# Low_Pass_Filter.net
KiCad netlist of a schematic drawn in Altium Designer
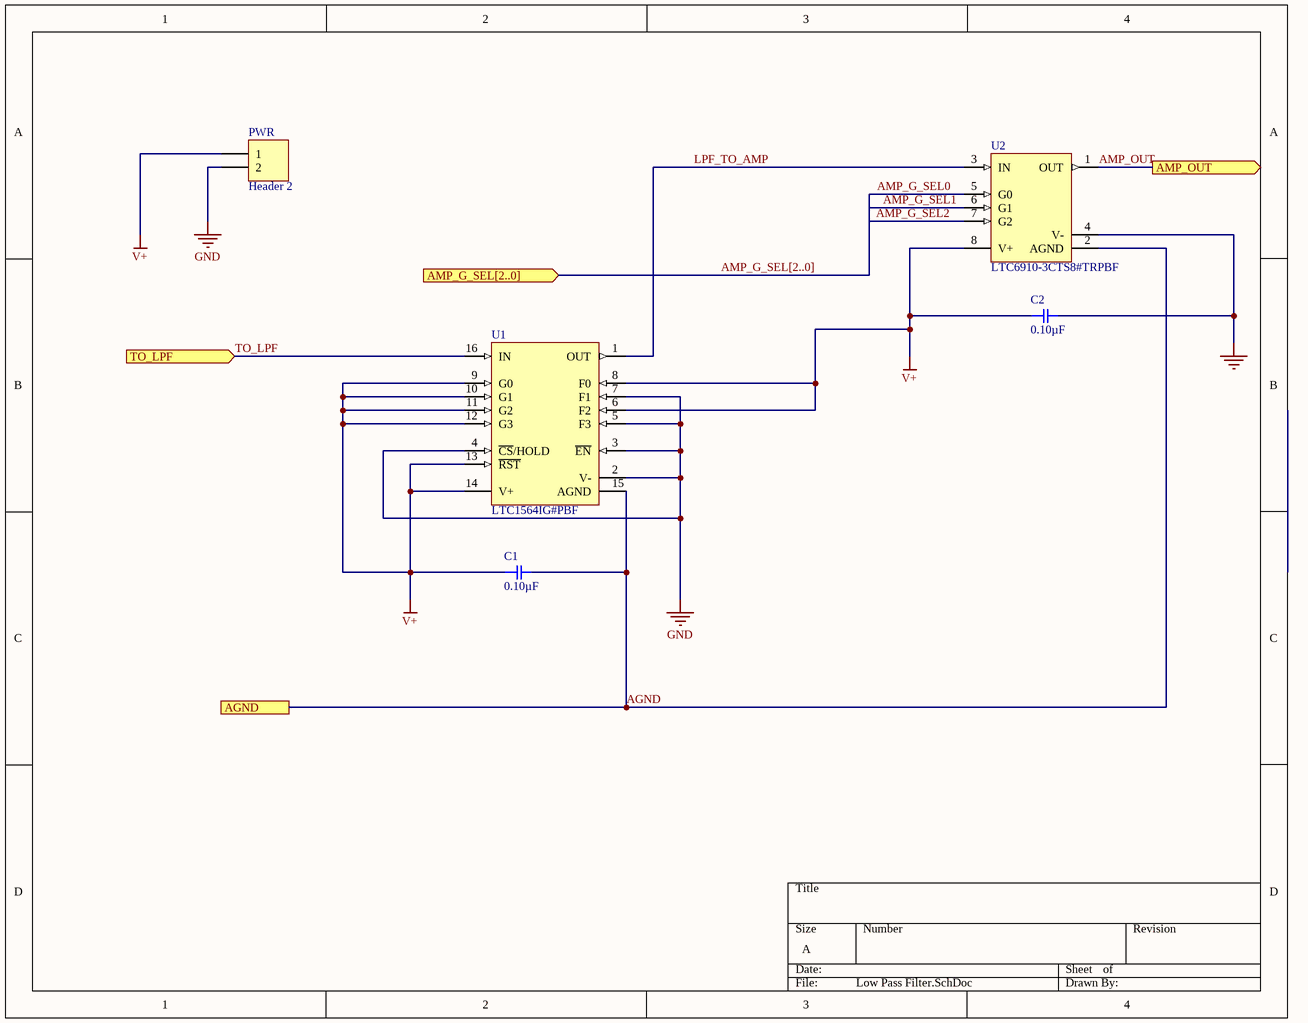
[diagram p0: Low Pass Filter.SchDoc]

(export (version "E")
  (design (tool "Eeschema 10.0.6"))
  (components
    (comp (ref "C1")
      (value "0.10µF")
      (footprint "SMD-0805C")
      (description "CAP CER 0.1UF 50V X7R 0805")
      (fields
        (field (name "DIGI-KEY PART NUMBER") "490-11955-1-ND")
        (field (name "PART NUMBER") "GCD21BR71H104KA01L")
      )
      (libsource (lib "capacitor_murata_0805") (part "GCD21BR71H104KA01L"))
    )
    (comp (ref "C2")
      (value "0.10µF")
      (footprint "SMD-0805C")
      (description "CAP CER 0.1UF 50V X7R 0805")
      (fields
        (field (name "DIGI-KEY PART NUMBER") "490-11955-1-ND")
        (field (name "PART NUMBER") "GCD21BR71H104KA01L")
      )
      (libsource (lib "capacitor_murata_0805") (part "GCD21BR71H104KA01L"))
    )
    (comp (ref "PWR")
      (value "Header 2")
      (footprint "HDR1X2")
      (description "Header, 2-Pin")
      (fields (field (name "PUBLISHER") "Altium Limited"))
      (libsource (lib "Miscellaneous Connectors") (part "Header 2"))
    )
    (comp (ref "U1")
      (value "LTC1564IG#PBF")
      (footprint "LT-G-16_M")
      (fields
        (field (name "LINEAR TECHNOLOGY PART NUMBER") "LTC1564")
        (field (name "MANUFACTURER") "Linear Technology")
      )
      (libsource (lib "Altium Content Vault") (part "LT-LTC1564-G-16"))
    )
    (comp (ref "U2")
      (value "LTC6910-3CTS8#TRPBF")
      (footprint "LT-TS8-8-TSOT-23_V")
      (fields
        (field (name "MANUFACTURER") "Linear Technology")
        (field (name "LINEAR TECHNOLOGY PART NUMBER") "LTC6910-3")
      )
      (libsource (lib "Altium Content Vault") (part "LT-LTC6910-TS8-8"))
    )
  )
  (nets
    (net (code "1") (name "/AGND") (class "Default")
      (node (ref "C1") (pin "2") (pinfunction "2_2") (pintype "passive"))
      (node (ref "U1") (pin "15") (pinfunction "AGND_15") (pintype "power_in"))
      (node (ref "U2") (pin "2") (pinfunction "AGND_2") (pintype "power_in"))
    )
    (net (code "2") (name "/AMP_G_SEL0") (class "Default")
      (node (ref "U2") (pin "5") (pinfunction "G0_5") (pintype "input"))
    )
    (net (code "3") (name "/AMP_G_SEL1") (class "Default")
      (node (ref "U2") (pin "6") (pinfunction "G1_6") (pintype "input"))
    )
    (net (code "4") (name "/AMP_G_SEL2") (class "Default")
      (node (ref "U2") (pin "7") (pinfunction "G2_7") (pintype "input"))
    )
    (net (code "6") (name "/AMP_OUT") (class "Default")
      (node (ref "U2") (pin "1") (pinfunction "OUT_1") (pintype "output"))
    )
    (net (code "7") (name "/LPF_TO_AMP") (class "Default")
      (node (ref "U1") (pin "1") (pinfunction "OUT_1") (pintype "output"))
      (node (ref "U2") (pin "3") (pinfunction "IN_3") (pintype "input"))
    )
    (net (code "8") (name "/TO_LPF") (class "Default")
      (node (ref "U1") (pin "16") (pinfunction "IN_16") (pintype "input"))
    )
    (net (code "9") (name "GND") (class "Default")
      (node (ref "C2") (pin "2") (pinfunction "2_2") (pintype "passive"))
      (node (ref "PWR") (pin "2") (pinfunction "2_2") (pintype "passive"))
      (node (ref "U1") (pin "2") (pinfunction "V-_2") (pintype "power_in"))
      (node (ref "U1") (pin "3") (pinfunction "~{EN}_3") (pintype "input"))
      (node (ref "U1") (pin "4") (pinfunction "~{CS}/HOLD_4") (pintype "input"))
      (node (ref "U1") (pin "5") (pinfunction "F3_5") (pintype "input"))
      (node (ref "U1") (pin "7") (pinfunction "F1_7") (pintype "input"))
      (node (ref "U2") (pin "4") (pinfunction "V-_4") (pintype "power_in"))
    )
    (net (code "10") (name "V+") (class "Default")
      (node (ref "C1") (pin "1") (pinfunction "1_1") (pintype "passive"))
      (node (ref "C2") (pin "1") (pinfunction "1_1") (pintype "passive"))
      (node (ref "PWR") (pin "1") (pinfunction "1_1") (pintype "passive"))
      (node (ref "U1") (pin "10") (pinfunction "G1_10") (pintype "input"))
      (node (ref "U1") (pin "11") (pinfunction "G2_11") (pintype "input"))
      (node (ref "U1") (pin "12") (pinfunction "G3_12") (pintype "input"))
      (node (ref "U1") (pin "13") (pinfunction "~{RST}_13") (pintype "input"))
      (node (ref "U1") (pin "14") (pinfunction "V+_14") (pintype "power_in"))
      (node (ref "U1") (pin "6") (pinfunction "F2_6") (pintype "input"))
      (node (ref "U1") (pin "8") (pinfunction "F0_8") (pintype "input"))
      (node (ref "U1") (pin "9") (pinfunction "G0_9") (pintype "input"))
      (node (ref "U2") (pin "8") (pinfunction "V+_8") (pintype "power_in"))
    )
  )
)
